# 26_PWR_3V3_1V0_CON.net
KiCad netlist of a schematic drawn in Altium Designer
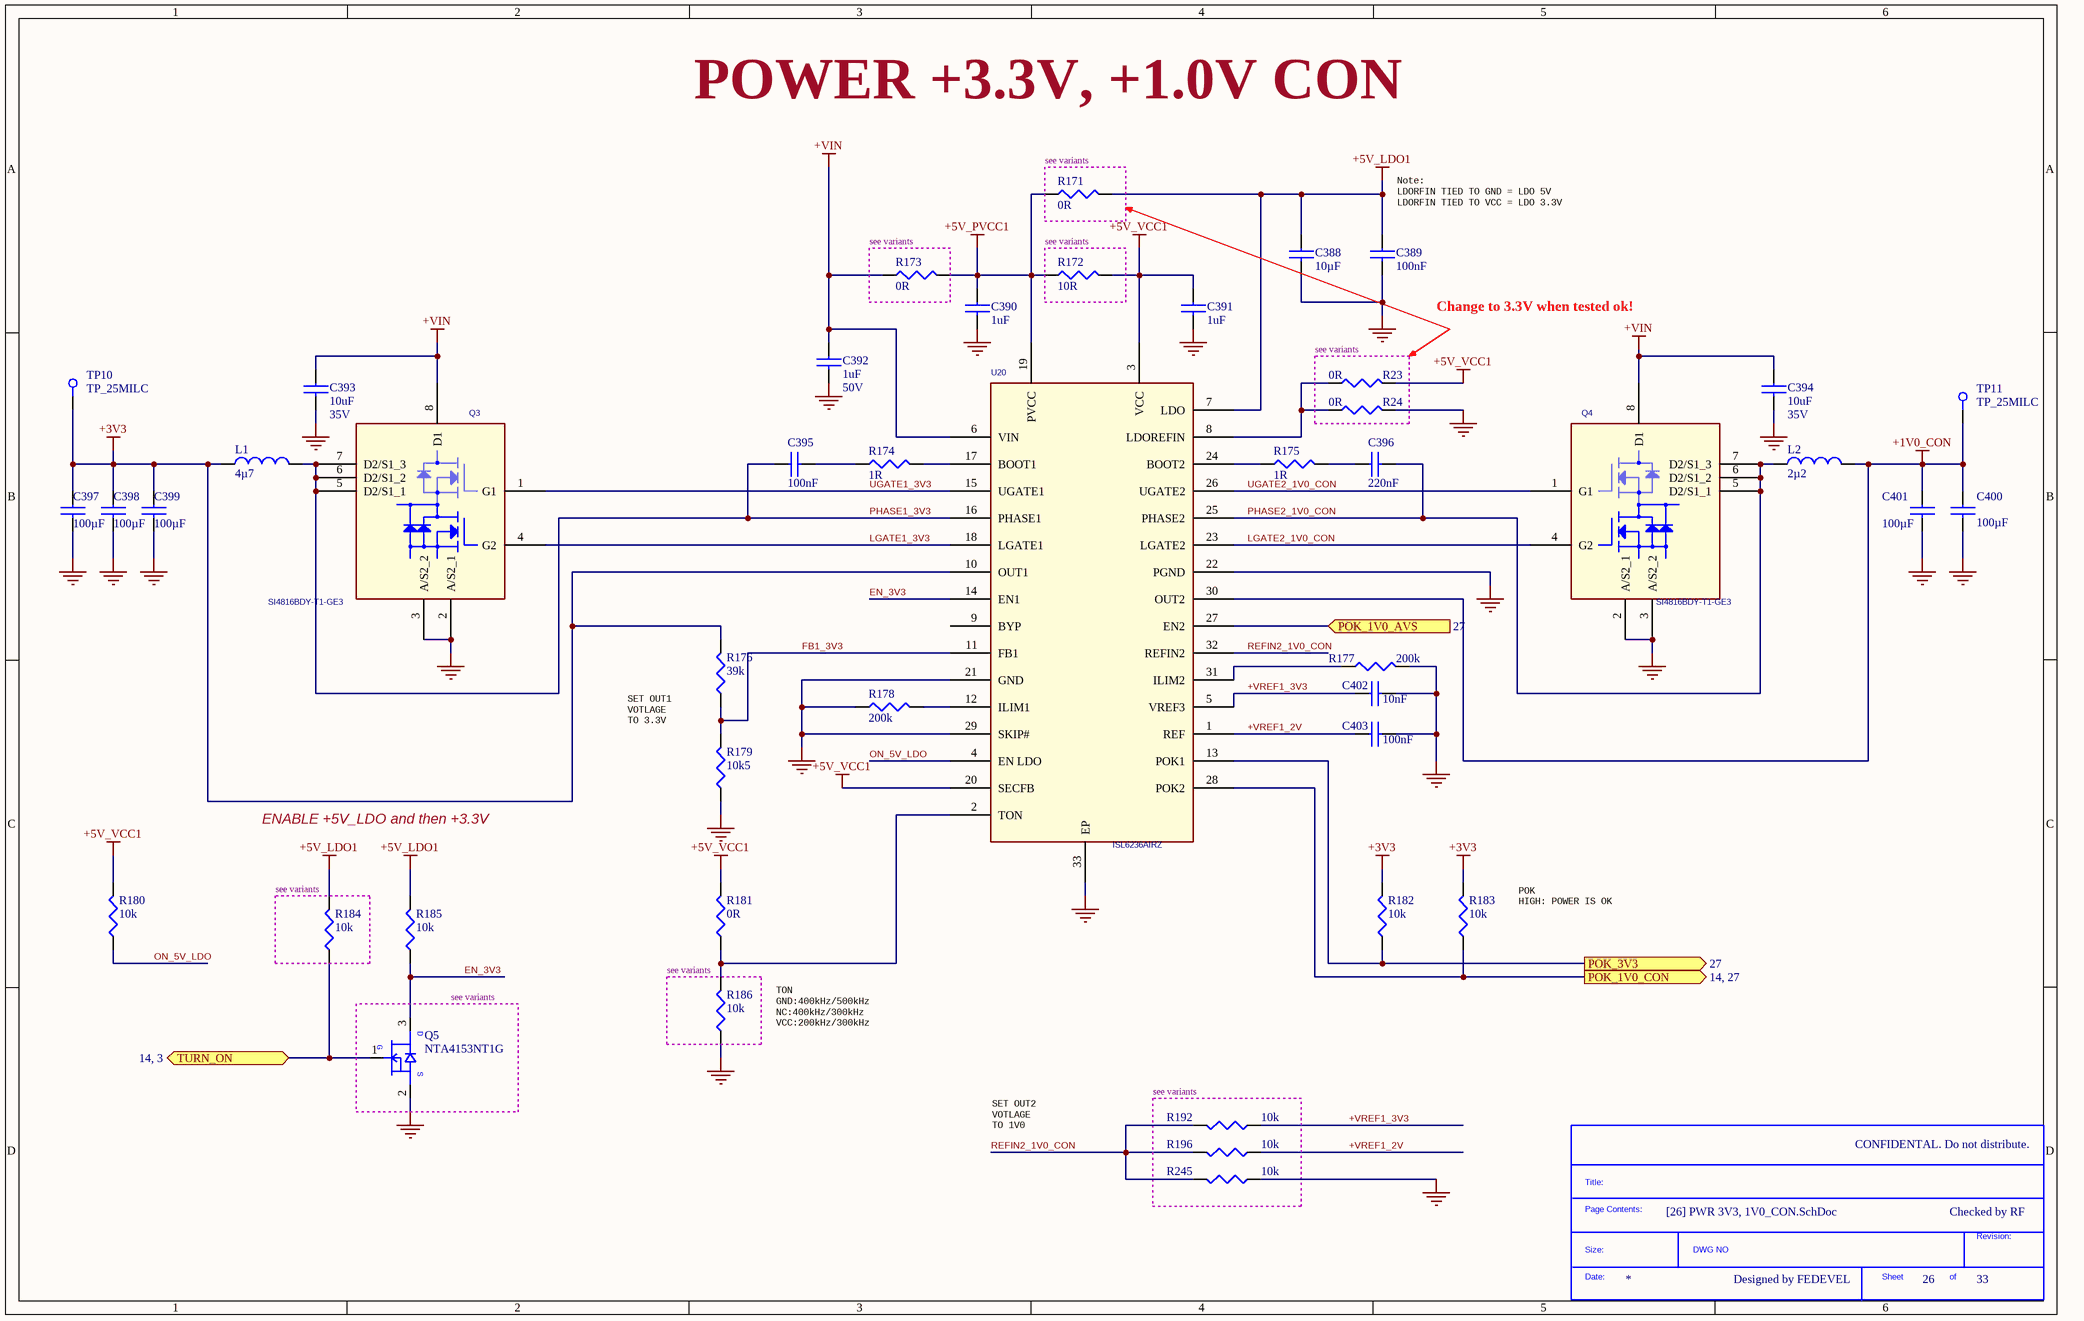
[diagram p0: [26] PWR 3V3, 1V0_CON.SchDoc]

(export (version "E")
  (design (tool "Eeschema 10.0.6"))
  (components
    (comp (ref "*") (value "SDTitleBlock") (libsource (lib "*") (part "SDTitleBlock")))
    (comp (ref "C388")
      (value "10µF")
      (footprint "C0603")
      (description "CAP CER 10UF 6.3V X5R 20% 0603")
      (fields
        (field (name "MANUFACTURER") "TDK Corporation")
        (field (name "MANUFACTURER PART NUMBER") "C1608X5R0J106M")
      )
      (libsource (lib "Integrated_Library_RF_FEB_2012") (part "C1608X5R0J106M"))
    )
    (comp (ref "C389")
      (value "100nF")
      (footprint "C0402")
      (description "CAP CER .10UF 50V X5R 10% 0402")
      (fields
        (field (name "MANUFACTURER") "TDK Corporation")
        (field (name "MANUFACTURER PART NUMBER") "C1005X5R1H104K")
      )
      (libsource (lib "Integrated_Library_RF_FEB_2012") (part "C1005X5R1H104K"))
    )
    (comp (ref "C390")
      (value "1uF")
      (footprint "C0402")
      (description "CAP CER 1.0UF 16V X5R 0402")
      (fields
        (field (name "MANUFACTURER") "TDK Corporation")
        (field (name "MANUFACTURER PART NUMBER") "C1005X5R1C105K")
      )
      (libsource (lib "Integrated_Library_RF_FEB_2012") (part "C1005X5R1C105K"))
    )
    (comp (ref "C391")
      (value "1uF")
      (footprint "C0402")
      (description "CAP CER 1.0UF 16V X5R 0402")
      (fields
        (field (name "MANUFACTURER") "TDK Corporation")
        (field (name "MANUFACTURER PART NUMBER") "C1005X5R1C105K")
      )
      (libsource (lib "Integrated_Library_RF_FEB_2012") (part "C1005X5R1C105K"))
    )
    (comp (ref "C392")
      (value "1uF")
      (footprint "C0805")
      (description "CAP CER 1UF 50V X7R 0805")
      (fields
        (field (name "MANUFACTURER") "Murata Electronics North America")
        (field (name "MANUFACTURER PART NUMBER") "GRM21BR71H105KA12L")
        (field (name "VOLTAGE - RATED") "50V")
      )
      (libsource (lib "Integrated_Library_RF_FEB_2012") (part "GRM21BR71H105KA12L"))
    )
    (comp (ref "C393")
      (value "10uF")
      (footprint "C1206")
      (description "CAP CER 10UF 35V X5R 1206")
      (fields
        (field (name "MANUFACTURER") "Murata Electronics North America")
        (field (name "MANUFACTURER PART NUMBER") "GRM31CR6YA106KA12L")
        (field (name "VOLTAGE - RATED") "35V")
      )
      (libsource (lib "Integrated_Library_RF_FEB_2012") (part "GRM31CR6YA106KA12L"))
    )
    (comp (ref "C394")
      (value "10uF")
      (footprint "C1206")
      (description "CAP CER 10UF 35V X5R 1206")
      (fields
        (field (name "MANUFACTURER") "Murata Electronics North America")
        (field (name "MANUFACTURER PART NUMBER") "GRM31CR6YA106KA12L")
        (field (name "VOLTAGE - RATED") "35V")
      )
      (libsource (lib "Integrated_Library_RF_FEB_2012") (part "GRM31CR6YA106KA12L"))
    )
    (comp (ref "C395")
      (value "100nF")
      (footprint "C0402")
      (description "CAP CER .10UF 50V X5R 10% 0402")
      (fields
        (field (name "MANUFACTURER") "TDK Corporation")
        (field (name "MANUFACTURER PART NUMBER") "C1005X5R1H104K")
      )
      (libsource (lib "Integrated_Library_RF_FEB_2012") (part "C1005X5R1H104K"))
    )
    (comp (ref "C396")
      (value "220nF")
      (footprint "C0402")
      (description "CAP CER .22UF 25V X5R 20% 0402")
      (fields
        (field (name "MANUFACTURER") "TDK Corporation")
        (field (name "MANUFACTURER PART NUMBER") "C1005X5R1E224M")
      )
      (libsource (lib "Integrated_Library_RF_FEB_2012") (part "C1005X5R1E224M"))
    )
    (comp (ref "C397")
      (value "100µF")
      (footprint "C1206")
      (description "CAP CER 100UF 10V X5R 20% 1206")
      (fields
        (field (name "MANUFACTURER") "TDK Corporation")
        (field (name "MANUFACTURER PART NUMBER") "C3216X5R1A107M")
      )
      (libsource (lib "Integrated_Library_RF_FEB_2012") (part "C3216X5R1A107M"))
    )
    (comp (ref "C398")
      (value "100µF")
      (footprint "C1206")
      (description "CAP CER 100UF 10V X5R 20% 1206")
      (fields
        (field (name "MANUFACTURER") "TDK Corporation")
        (field (name "MANUFACTURER PART NUMBER") "C3216X5R1A107M")
      )
      (libsource (lib "Integrated_Library_RF_FEB_2012") (part "C3216X5R1A107M"))
    )
    (comp (ref "C399")
      (value "100µF")
      (footprint "C1206")
      (description "CAP CER 100UF 10V X5R 20% 1206")
      (fields
        (field (name "MANUFACTURER") "TDK Corporation")
        (field (name "MANUFACTURER PART NUMBER") "C3216X5R1A107M")
      )
      (libsource (lib "Integrated_Library_RF_FEB_2012") (part "C3216X5R1A107M"))
    )
    (comp (ref "C400")
      (value "100µF")
      (footprint "C1206")
      (description "CAP CER 100UF 10V X5R 20% 1206")
      (fields
        (field (name "MANUFACTURER") "TDK Corporation")
        (field (name "MANUFACTURER PART NUMBER") "C3216X5R1A107M")
      )
      (libsource (lib "Integrated_Library_RF_FEB_2012") (part "C3216X5R1A107M"))
    )
    (comp (ref "C401")
      (value "100µF")
      (footprint "C1206")
      (description "CAP CER 100UF 10V X5R 20% 1206")
      (fields
        (field (name "MANUFACTURER") "TDK Corporation")
        (field (name "MANUFACTURER PART NUMBER") "C3216X5R1A107M")
      )
      (libsource (lib "Integrated_Library_RF_FEB_2012") (part "C3216X5R1A107M"))
    )
    (comp (ref "C402")
      (value "10nF")
      (footprint "C0402")
      (description "CAP CER 10000PF 16V X7R 10% 0402")
      (fields
        (field (name "MANUFACTURER") "TDK Corporation")
        (field (name "MANUFACTURER PART NUMBER") "C1005X7R1C103K")
      )
      (libsource (lib "Integrated_Library_RF_FEB_2012") (part "C1005X7R1C103K"))
    )
    (comp (ref "C403")
      (value "100nF")
      (footprint "C0402")
      (description "CAP CER .10UF 50V X5R 10% 0402")
      (fields
        (field (name "MANUFACTURER") "TDK Corporation")
        (field (name "MANUFACTURER PART NUMBER") "C1005X5R1H104K")
      )
      (libsource (lib "Integrated_Library_RF_FEB_2012") (part "C1005X5R1H104K"))
    )
    (comp (ref "L1")
      (value "4µ7")
      (footprint "IHLP_255MILx270MIL")
      (description "INDUCTOR POWER 4.7UH 5.5A SMD")
      (fields
        (field (name "MANUFACTURER") "Vishay/Dale")
        (field (name "MANUFACTURER PART NUMBER") "IHLP2525CZER4R7M01")
      )
      (libsource (lib "Integrated_Library_RF_FEB_2012") (part "IHLP2525CZER4R7M01"))
    )
    (comp (ref "L2")
      (value "2µ2")
      (footprint "IHLP_255MILx270MIL")
      (description "INDUCTOR POWER 2.2UH 8A SMD")
      (fields
        (field (name "MANUFACTURER") "Vishay/Dale")
        (field (name "MANUFACTURER PART NUMBER") "IHLP2525CZER2R2M01")
      )
      (libsource (lib "Integrated_Library_RF_FEB_2012") (part "IHLP2525CZER2R2M01"))
    )
    (comp (ref "Q3")
      (value "SI4816BDY-T1-GE3")
      (footprint "8_SOIC_3.9MM")
      (description "MOSFET DL N-CH 30V 6.8A 8-SOIC")
      (fields (field (name "MANUFACTURER") "Vishay/Siliconix"))
      (libsource (lib "Integrated_Library_RF_FEB_2012") (part "SI4816BDY-T1-GE3"))
    )
    (comp (ref "Q4")
      (value "SI4816BDY-T1-GE3")
      (footprint "8_SOIC_3.9MM")
      (description "MOSFET DL N-CH 30V 6.8A 8-SOIC")
      (fields (field (name "MANUFACTURER") "Vishay/Siliconix"))
      (libsource (lib "Integrated_Library_RF_FEB_2012") (part "SI4816BDY-T1-GE3"))
    )
    (comp (ref "Q5")
      (value "NTA4153NT1G")
      (footprint "SC-75_SOT-416")
      (description "MOSFET N-CH 20V 915MA SOT-416")
      (fields (field (name "MANUFACTURER") "ON Semiconductor"))
      (libsource (lib "Integrated_Library_RF_FEB_2012") (part "NTA4153NT1G"))
    )
    (comp (ref "R23")
      (value "0R")
      (footprint "R0402")
      (description "RES 0.0 OHM 1/16W 0402 SMD")
      (fields
        (field (name "MANUFACTURER") "Yageo")
        (field (name "MANUFACTURER PART NUMBER") "RC0402JR-070RL")
      )
      (libsource (lib "Integrated_Library_RF_FEB_2012") (part "RC0402JR-070RL"))
    )
    (comp (ref "R24")
      (value "0R")
      (footprint "R0402")
      (description "RES 0.0 OHM 1/16W 0402 SMD")
      (fields
        (field (name "MANUFACTURER") "Yageo")
        (field (name "MANUFACTURER PART NUMBER") "RC0402JR-070RL")
      )
      (libsource (lib "Integrated_Library_RF_FEB_2012") (part "RC0402JR-070RL"))
    )
    (comp (ref "R171")
      (value "0R")
      (footprint "R0402")
      (description "RES 0.0 OHM 1/16W 0402 SMD")
      (fields
        (field (name "MANUFACTURER") "Yageo")
        (field (name "MANUFACTURER PART NUMBER") "RC0402JR-070RL")
      )
      (libsource (lib "Integrated_Library_RF_FEB_2012") (part "RC0402JR-070RL"))
    )
    (comp (ref "R172")
      (value "10R")
      (footprint "R0402")
      (description "RES 10.0 OHM 1/16W 1% 0402 SMD")
      (fields
        (field (name "MANUFACTURER") "Yageo")
        (field (name "MANUFACTURER PART NUMBER") "RC0402FR-0710RL")
      )
      (libsource (lib "Integrated_Library_RF_FEB_2012") (part "RC0402FR-0710RL"))
    )
    (comp (ref "R173")
      (value "0R")
      (footprint "R0402")
      (description "RES 0.0 OHM 1/16W 0402 SMD")
      (fields
        (field (name "MANUFACTURER") "Yageo")
        (field (name "MANUFACTURER PART NUMBER") "RC0402JR-070RL")
      )
      (libsource (lib "Integrated_Library_RF_FEB_2012") (part "RC0402JR-070RL"))
    )
    (comp (ref "R174")
      (value "1R")
      (footprint "R0402")
      (description "RES 1.00 OHM 1/16W 1% 0402 SM")
      (fields
        (field (name "MANUFACTURER") "Yageo")
        (field (name "MANUFACTURER PART NUMBER") "RC0402FR-071RL")
      )
      (libsource (lib "Integrated_Library_RF_FEB_2012") (part "RC0402FR-071RL"))
    )
    (comp (ref "R175")
      (value "1R")
      (footprint "R0402")
      (description "RES 1.00 OHM 1/16W 1% 0402 SM")
      (fields
        (field (name "MANUFACTURER") "Yageo")
        (field (name "MANUFACTURER PART NUMBER") "RC0402FR-071RL")
      )
      (libsource (lib "Integrated_Library_RF_FEB_2012") (part "RC0402FR-071RL"))
    )
    (comp (ref "R176")
      (value "39k")
      (footprint "R0402")
      (description "RES 39.0K OHM 1/16W 1% 0402 SMD")
      (fields
        (field (name "MANUFACTURER") "Yageo")
        (field (name "MANUFACTURER PART NUMBER") "RC0402FR-0739KL")
      )
      (libsource (lib "Integrated_Library_RF_FEB_2012") (part "RC0402FR-0739KL"))
    )
    (comp (ref "R177")
      (value "200k")
      (footprint "R0402")
      (description "RES 200K OHM 1/16W 1% 0402 SMD")
      (fields
        (field (name "MANUFACTURER") "Yageo")
        (field (name "MANUFACTURER PART NUMBER") "RC0402FR-07200KL")
      )
      (libsource (lib "Integrated_Library_RF_FEB_2012") (part "RC0402FR-07200KL"))
    )
    (comp (ref "R178")
      (value "200k")
      (footprint "R0402")
      (description "RES 200K OHM 1/16W 1% 0402 SMD")
      (fields
        (field (name "MANUFACTURER") "Yageo")
        (field (name "MANUFACTURER PART NUMBER") "RC0402FR-07200KL")
      )
      (libsource (lib "Integrated_Library_RF_FEB_2012") (part "RC0402FR-07200KL"))
    )
    (comp (ref "R179")
      (value "10k5")
      (footprint "R0402")
      (description "RES 10.5K OHM 1/16W 1% 0402 SMD")
      (fields
        (field (name "MANUFACTURER") "Vishay/Dale")
        (field (name "MANUFACTURER PART NUMBER") "CRCW040210K5FKED")
      )
      (libsource (lib "Integrated_Library_RF_FEB_2012") (part "CRCW040210K5FKED"))
    )
    (comp (ref "R180")
      (value "10k")
      (footprint "R0402")
      (description "RES 10.0K OHM 1/16W 1% 0402 SMD")
      (fields
        (field (name "MANUFACTURER") "Yageo")
        (field (name "MANUFACTURER PART NUMBER") "RC0402FR-0710KL")
      )
      (libsource (lib "Integrated_Library_RF_FEB_2012") (part "RC0402FR-0710KL"))
    )
    (comp (ref "R181")
      (value "0R")
      (footprint "R0402")
      (description "RES 0.0 OHM 1/16W 0402 SMD")
      (fields
        (field (name "MANUFACTURER") "Yageo")
        (field (name "MANUFACTURER PART NUMBER") "RC0402JR-070RL")
      )
      (libsource (lib "Integrated_Library_RF_FEB_2012") (part "RC0402JR-070RL"))
    )
    (comp (ref "R182")
      (value "10k")
      (footprint "R0402")
      (description "RES 10.0K OHM 1/16W 1% 0402 SMD")
      (fields
        (field (name "MANUFACTURER") "Yageo")
        (field (name "MANUFACTURER PART NUMBER") "RC0402FR-0710KL")
      )
      (libsource (lib "Integrated_Library_RF_FEB_2012") (part "RC0402FR-0710KL"))
    )
    (comp (ref "R183")
      (value "10k")
      (footprint "R0402")
      (description "RES 10.0K OHM 1/16W 1% 0402 SMD")
      (fields
        (field (name "MANUFACTURER") "Yageo")
        (field (name "MANUFACTURER PART NUMBER") "RC0402FR-0710KL")
      )
      (libsource (lib "Integrated_Library_RF_FEB_2012") (part "RC0402FR-0710KL"))
    )
    (comp (ref "R184")
      (value "10k")
      (footprint "R0402")
      (description "RES 10.0K OHM 1/16W 1% 0402 SMD")
      (fields
        (field (name "MANUFACTURER") "Yageo")
        (field (name "MANUFACTURER PART NUMBER") "RC0402FR-0710KL")
      )
      (libsource (lib "Integrated_Library_RF_FEB_2012") (part "RC0402FR-0710KL"))
    )
    (comp (ref "R185")
      (value "10k")
      (footprint "R0402")
      (description "RES 10.0K OHM 1/16W 1% 0402 SMD")
      (fields
        (field (name "MANUFACTURER") "Yageo")
        (field (name "MANUFACTURER PART NUMBER") "RC0402FR-0710KL")
      )
      (libsource (lib "Integrated_Library_RF_FEB_2012") (part "RC0402FR-0710KL"))
    )
    (comp (ref "R186")
      (value "10k")
      (footprint "R0402")
      (description "RES 10.0K OHM 1/16W 1% 0402 SMD")
      (fields
        (field (name "MANUFACTURER") "Yageo")
        (field (name "MANUFACTURER PART NUMBER") "RC0402FR-0710KL")
      )
      (libsource (lib "Integrated_Library_RF_FEB_2012") (part "RC0402FR-0710KL"))
    )
    (comp (ref "R192")
      (value "10k")
      (footprint "R0402")
      (description "RES 10.0K OHM 1/16W 1% 0402 SMD")
      (fields
        (field (name "MANUFACTURER") "Yageo")
        (field (name "MANUFACTURER PART NUMBER") "RC0402FR-0710KL")
      )
      (libsource (lib "Integrated_Library_RF_FEB_2012") (part "RC0402FR-0710KL"))
    )
    (comp (ref "R196")
      (value "10k")
      (footprint "R0402")
      (description "RES 10.0K OHM 1/16W 1% 0402 SMD")
      (fields
        (field (name "MANUFACTURER") "Yageo")
        (field (name "MANUFACTURER PART NUMBER") "RC0402FR-0710KL")
      )
      (libsource (lib "Integrated_Library_RF_FEB_2012") (part "RC0402FR-0710KL"))
    )
    (comp (ref "R245")
      (value "10k")
      (footprint "R0402")
      (description "RES 10.0K OHM 1/16W 1% 0402 SMD")
      (fields
        (field (name "MANUFACTURER") "Yageo")
        (field (name "MANUFACTURER PART NUMBER") "RC0402FR-0710KL")
      )
      (libsource (lib "Integrated_Library_RF_FEB_2012") (part "RC0402FR-0710KL"))
    )
    (comp (ref "TP10")
      (value "TP_25MILC")
      (footprint "TP_25C")
      (description "Test Point 25mil")
      (libsource (lib "Integrated_Library_RF_FEB_2012") (part "TP_25MILC"))
    )
    (comp (ref "TP11")
      (value "TP_25MILC")
      (footprint "TP_25C")
      (description "Test Point 25mil")
      (libsource (lib "Integrated_Library_RF_FEB_2012") (part "TP_25MILC"))
    )
    (comp (ref "U20")
      (value "ISL6236AIRZ")
      (footprint "32_VFQFN_EXPOSED_PAD")
      (description "IC MAIN PWR CTRLR QUAD 32-QFN")
      (fields (field (name "MANUFACTURER") "Intersil"))
      (libsource (lib "Integrated_Library_RF_FEB_2012") (part "ISL6236AIRZ"))
    )
  )
  (nets
    (net (code "1") (name "+1V0_CON") (class "Default")
      (node (ref "C400") (pin "1") (pinfunction "1_1") (pintype "passive"))
      (node (ref "C401") (pin "1") (pinfunction "1_1") (pintype "passive"))
      (node (ref "L2") (pin "2") (pinfunction "2_2") (pintype "passive"))
      (node (ref "TP11") (pin "1") (pinfunction "1_1") (pintype "passive"))
      (node (ref "U20") (pin "30") (pinfunction "OUT2_30") (pintype "passive"))
    )
    (net (code "2") (name "+3V3") (class "Default")
      (node (ref "C397") (pin "1") (pinfunction "1_1") (pintype "passive"))
      (node (ref "C398") (pin "1") (pinfunction "1_1") (pintype "passive"))
      (node (ref "C399") (pin "1") (pinfunction "1_1") (pintype "passive"))
      (node (ref "L1") (pin "1") (pinfunction "1_1") (pintype "passive"))
      (node (ref "R176") (pin "2") (pinfunction "2_2") (pintype "passive"))
      (node (ref "R182") (pin "2") (pinfunction "2_2") (pintype "passive"))
      (node (ref "R183") (pin "2") (pinfunction "2_2") (pintype "passive"))
      (node (ref "TP10") (pin "1") (pinfunction "1_1") (pintype "passive"))
      (node (ref "U20") (pin "10") (pinfunction "OUT1_10") (pintype "passive"))
    )
    (net (code "3") (name "+5V_LDO1") (class "Default")
      (node (ref "C388") (pin "1") (pinfunction "1_1") (pintype "passive"))
      (node (ref "C389") (pin "1") (pinfunction "1_1") (pintype "passive"))
      (node (ref "R171") (pin "2") (pinfunction "2_2") (pintype "passive"))
      (node (ref "R184") (pin "2") (pinfunction "2_2") (pintype "passive"))
      (node (ref "R185") (pin "2") (pinfunction "2_2") (pintype "passive"))
      (node (ref "U20") (pin "7") (pinfunction "LDO_7") (pintype "passive"))
    )
    (net (code "4") (name "+5V_PVCC1") (class "Default")
      (node (ref "C390") (pin "1") (pinfunction "1_1") (pintype "passive"))
      (node (ref "R171") (pin "1") (pinfunction "1_1") (pintype "passive"))
      (node (ref "R172") (pin "1") (pinfunction "1_1") (pintype "passive"))
      (node (ref "R173") (pin "2") (pinfunction "2_2") (pintype "passive"))
      (node (ref "U20") (pin "19") (pinfunction "PVCC_19") (pintype "passive"))
    )
    (net (code "5") (name "+5V_VCC1") (class "Default")
      (node (ref "C391") (pin "1") (pinfunction "1_1") (pintype "passive"))
      (node (ref "R172") (pin "2") (pinfunction "2_2") (pintype "passive"))
      (node (ref "R180") (pin "2") (pinfunction "2_2") (pintype "passive"))
      (node (ref "R181") (pin "2") (pinfunction "2_2") (pintype "passive"))
      (node (ref "R23") (pin "2") (pinfunction "2_2") (pintype "passive"))
      (node (ref "U20") (pin "20") (pinfunction "SECFB_20") (pintype "passive"))
      (node (ref "U20") (pin "3") (pinfunction "VCC_3") (pintype "passive"))
    )
    (net (code "6") (name "+VIN") (class "Default")
      (node (ref "C392") (pin "1") (pinfunction "1_1") (pintype "passive"))
      (node (ref "C393") (pin "1") (pinfunction "1_1") (pintype "passive"))
      (node (ref "C394") (pin "1") (pinfunction "1_1") (pintype "passive"))
      (node (ref "Q3") (pin "8") (pinfunction "D1_8") (pintype "passive"))
      (node (ref "Q4") (pin "8") (pinfunction "D1_8") (pintype "passive"))
      (node (ref "R173") (pin "1") (pinfunction "1_1") (pintype "passive"))
      (node (ref "U20") (pin "6") (pinfunction "VIN_6") (pintype "passive"))
    )
    (net (code "7") (name "/+VREF1_2V") (class "Default")
      (node (ref "C403") (pin "1") (pinfunction "1_1") (pintype "passive"))
      (node (ref "R196") (pin "1") (pinfunction "1_1") (pintype "passive"))
      (node (ref "U20") (pin "1") (pinfunction "REF_1") (pintype "passive"))
    )
    (net (code "8") (name "/+VREF1_3V3") (class "Default")
      (node (ref "C402") (pin "1") (pinfunction "1_1") (pintype "passive"))
      (node (ref "R192") (pin "1") (pinfunction "1_1") (pintype "passive"))
      (node (ref "U20") (pin "5") (pinfunction "VREF3_5") (pintype "passive"))
    )
    (net (code "9") (name "/EN_3V3") (class "Default")
      (node (ref "Q5") (pin "3") (pinfunction "DRAIN_3") (pintype "passive"))
      (node (ref "R185") (pin "1") (pinfunction "1_1") (pintype "passive"))
      (node (ref "U20") (pin "14") (pinfunction "EN1_14") (pintype "passive"))
    )
    (net (code "10") (name "/FB1_3V3") (class "Default")
      (node (ref "R176") (pin "1") (pinfunction "1_1") (pintype "passive"))
      (node (ref "R179") (pin "2") (pinfunction "2_2") (pintype "passive"))
      (node (ref "U20") (pin "11") (pinfunction "FB1_11") (pintype "passive"))
    )
    (net (code "11") (name "/LGATE1_3V3") (class "Default")
      (node (ref "Q3") (pin "4") (pinfunction "G2_4") (pintype "passive"))
      (node (ref "U20") (pin "18") (pinfunction "LGATE1_18") (pintype "passive"))
    )
    (net (code "12") (name "/LGATE2_1V0_CON") (class "Default")
      (node (ref "Q4") (pin "4") (pinfunction "G2_4") (pintype "passive"))
      (node (ref "U20") (pin "23") (pinfunction "LGATE2_23") (pintype "passive"))
    )
    (net (code "13") (name "/ON_5V_LDO") (class "Default")
      (node (ref "R180") (pin "1") (pinfunction "1_1") (pintype "passive"))
      (node (ref "U20") (pin "4") (pinfunction "EN_LDO_4") (pintype "passive"))
    )
    (net (code "14") (name "/PHASE1_3V3") (class "Default")
      (node (ref "C395") (pin "1") (pinfunction "1_1") (pintype "passive"))
      (node (ref "L1") (pin "2") (pinfunction "2_2") (pintype "passive"))
      (node (ref "Q3") (pin "5") (pinfunction "D2/S1_1_5") (pintype "passive"))
      (node (ref "Q3") (pin "6") (pinfunction "D2/S1_2_6") (pintype "passive"))
      (node (ref "Q3") (pin "7") (pinfunction "D2/S1_3_7") (pintype "passive"))
      (node (ref "U20") (pin "16") (pinfunction "PHASE1_16") (pintype "passive"))
    )
    (net (code "15") (name "/PHASE2_1V0_CON") (class "Default")
      (node (ref "C396") (pin "2") (pinfunction "2_2") (pintype "passive"))
      (node (ref "L2") (pin "1") (pinfunction "1_1") (pintype "passive"))
      (node (ref "Q4") (pin "5") (pinfunction "D2/S1_1_5") (pintype "passive"))
      (node (ref "Q4") (pin "6") (pinfunction "D2/S1_2_6") (pintype "passive"))
      (node (ref "Q4") (pin "7") (pinfunction "D2/S1_3_7") (pintype "passive"))
      (node (ref "U20") (pin "25") (pinfunction "PHASE2_25") (pintype "passive"))
    )
    (net (code "16") (name "/POK_1V0_AVS") (class "Default")
      (node (ref "U20") (pin "27") (pinfunction "EN2_27") (pintype "passive"))
    )
    (net (code "17") (name "/POK_1V0_CON") (class "Default")
      (node (ref "R183") (pin "1") (pinfunction "1_1") (pintype "passive"))
      (node (ref "U20") (pin "28") (pinfunction "POK2_28") (pintype "passive"))
    )
    (net (code "18") (name "/POK_3V3") (class "Default")
      (node (ref "R182") (pin "1") (pinfunction "1_1") (pintype "passive"))
      (node (ref "U20") (pin "13") (pinfunction "POK1_13") (pintype "passive"))
    )
    (net (code "19") (name "/REFIN2_1V0_CON") (class "Default")
      (node (ref "R192") (pin "2") (pinfunction "2_2") (pintype "passive"))
      (node (ref "R196") (pin "2") (pinfunction "2_2") (pintype "passive"))
      (node (ref "R245") (pin "2") (pinfunction "2_2") (pintype "passive"))
      (node (ref "U20") (pin "32") (pinfunction "REFIN2_32") (pintype "passive"))
    )
    (net (code "20") (name "/TURN_ON") (class "Default")
      (node (ref "Q5") (pin "1") (pinfunction "GATE_1") (pintype "passive"))
      (node (ref "R184") (pin "1") (pinfunction "1_1") (pintype "passive"))
    )
    (net (code "21") (name "/UGATE1_3V3") (class "Default")
      (node (ref "Q3") (pin "1") (pinfunction "G1_1") (pintype "passive"))
      (node (ref "U20") (pin "15") (pinfunction "UGATE1_15") (pintype "passive"))
    )
    (net (code "22") (name "/UGATE2_1V0_CON") (class "Default")
      (node (ref "Q4") (pin "1") (pinfunction "G1_1") (pintype "passive"))
      (node (ref "U20") (pin "26") (pinfunction "UGATE2_26") (pintype "passive"))
    )
    (net (code "23") (name "GND") (class "Default")
      (node (ref "C388") (pin "2") (pinfunction "2_2") (pintype "passive"))
      (node (ref "C389") (pin "2") (pinfunction "2_2") (pintype "passive"))
      (node (ref "C390") (pin "2") (pinfunction "2_2") (pintype "passive"))
      (node (ref "C391") (pin "2") (pinfunction "2_2") (pintype "passive"))
      (node (ref "C392") (pin "2") (pinfunction "2_2") (pintype "passive"))
      (node (ref "C393") (pin "2") (pinfunction "2_2") (pintype "passive"))
      (node (ref "C394") (pin "2") (pinfunction "2_2") (pintype "passive"))
      (node (ref "C397") (pin "2") (pinfunction "2_2") (pintype "passive"))
      (node (ref "C398") (pin "2") (pinfunction "2_2") (pintype "passive"))
      (node (ref "C399") (pin "2") (pinfunction "2_2") (pintype "passive"))
      (node (ref "C400") (pin "2") (pinfunction "2_2") (pintype "passive"))
      (node (ref "C401") (pin "2") (pinfunction "2_2") (pintype "passive"))
      (node (ref "C402") (pin "2") (pinfunction "2_2") (pintype "passive"))
      (node (ref "C403") (pin "2") (pinfunction "2_2") (pintype "passive"))
      (node (ref "Q3") (pin "2") (pinfunction "A/S2_1_2") (pintype "passive"))
      (node (ref "Q3") (pin "3") (pinfunction "A/S2_2_3") (pintype "passive"))
      (node (ref "Q4") (pin "2") (pinfunction "A/S2_1_2") (pintype "passive"))
      (node (ref "Q4") (pin "3") (pinfunction "A/S2_2_3") (pintype "passive"))
      (node (ref "Q5") (pin "2") (pinfunction "SOURCE_2") (pintype "passive"))
      (node (ref "R177") (pin "2") (pinfunction "2_2") (pintype "passive"))
      (node (ref "R178") (pin "1") (pinfunction "1_1") (pintype "passive"))
      (node (ref "R179") (pin "1") (pinfunction "1_1") (pintype "passive"))
      (node (ref "R186") (pin "1") (pinfunction "1_1") (pintype "passive"))
      (node (ref "R24") (pin "2") (pinfunction "2_2") (pintype "passive"))
      (node (ref "R245") (pin "1") (pinfunction "1_1") (pintype "passive"))
      (node (ref "U20") (pin "21") (pinfunction "GND_21") (pintype "passive"))
      (node (ref "U20") (pin "22") (pinfunction "PGND_22") (pintype "passive"))
      (node (ref "U20") (pin "29") (pinfunction "SKIP#_29") (pintype "passive"))
      (node (ref "U20") (pin "33") (pinfunction "EP_33") (pintype "passive"))
    )
    (net (code "24") (name "Net-(C395-Pad2)") (class "Default")
      (node (ref "C395") (pin "2") (pinfunction "2_2") (pintype "passive"))
      (node (ref "R174") (pin "1") (pinfunction "1_1") (pintype "passive"))
    )
    (net (code "25") (name "Net-(C396-Pad1)") (class "Default")
      (node (ref "C396") (pin "1") (pinfunction "1_1") (pintype "passive"))
      (node (ref "R175") (pin "2") (pinfunction "2_2") (pintype "passive"))
    )
    (net (code "26") (name "Net-(U20-BOOT1)") (class "Default")
      (node (ref "R174") (pin "2") (pinfunction "2_2") (pintype "passive"))
      (node (ref "U20") (pin "17") (pinfunction "BOOT1_17") (pintype "passive"))
    )
    (net (code "27") (name "Net-(U20-BOOT2)") (class "Default")
      (node (ref "R175") (pin "1") (pinfunction "1_1") (pintype "passive"))
      (node (ref "U20") (pin "24") (pinfunction "BOOT2_24") (pintype "passive"))
    )
    (net (code "28") (name "Net-(U20-ILIM1)") (class "Default")
      (node (ref "R178") (pin "2") (pinfunction "2_2") (pintype "passive"))
      (node (ref "U20") (pin "12") (pinfunction "ILIM1_12") (pintype "passive"))
    )
    (net (code "29") (name "Net-(U20-ILIM2)") (class "Default")
      (node (ref "R177") (pin "1") (pinfunction "1_1") (pintype "passive"))
      (node (ref "U20") (pin "31") (pinfunction "ILIM2_31") (pintype "passive"))
    )
    (net (code "30") (name "Net-(U20-LDOREFIN)") (class "Default")
      (node (ref "R23") (pin "1") (pinfunction "1_1") (pintype "passive"))
      (node (ref "R24") (pin "1") (pinfunction "1_1") (pintype "passive"))
      (node (ref "U20") (pin "8") (pinfunction "LDOREFIN_8") (pintype "passive"))
    )
    (net (code "31") (name "Net-(U20-TON)") (class "Default")
      (node (ref "R181") (pin "1") (pinfunction "1_1") (pintype "passive"))
      (node (ref "R186") (pin "2") (pinfunction "2_2") (pintype "passive"))
      (node (ref "U20") (pin "2") (pinfunction "TON_2") (pintype "passive"))
    )
    (net (code "32") (name "unconnected-(U20-BYP-Pad9)") (class "Default")
      (node (ref "U20") (pin "9") (pinfunction "BYP_9") (pintype "passive"))
    )
  )
)
